# CoffeePID_EDA.net
KiCad netlist of a schematic drawn in EasyEDA
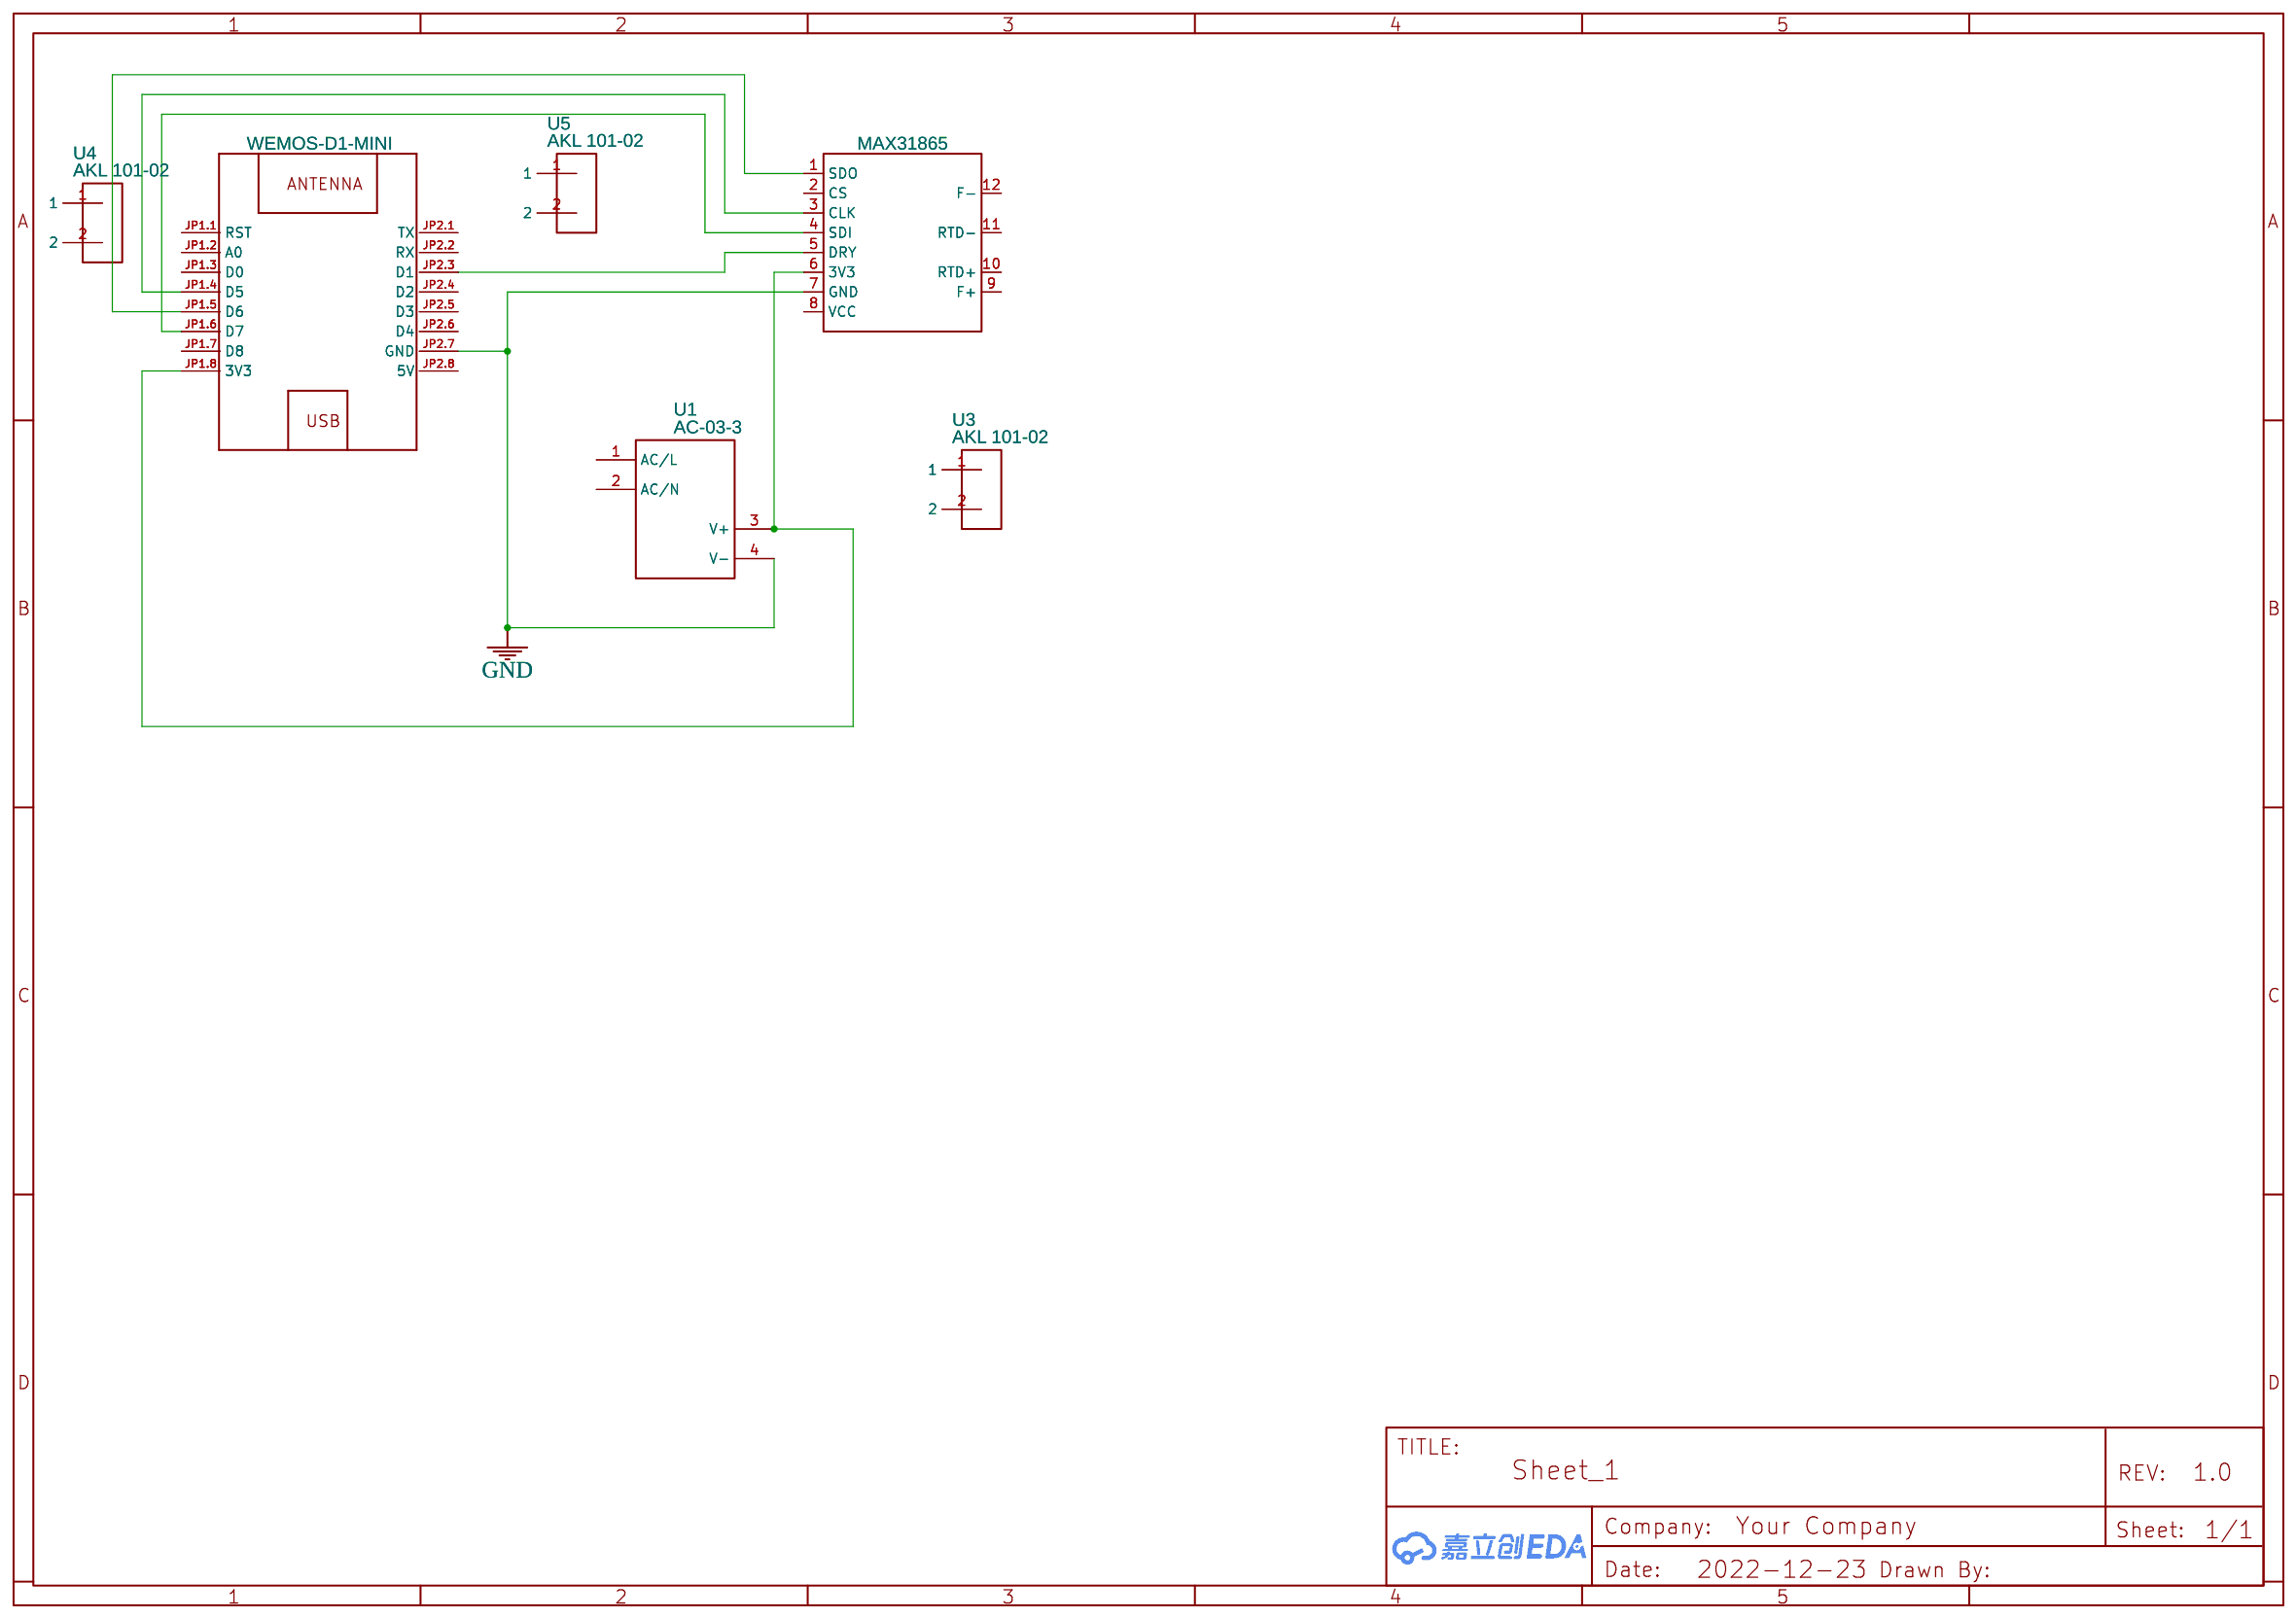
[diagram p0: Wemos D1]
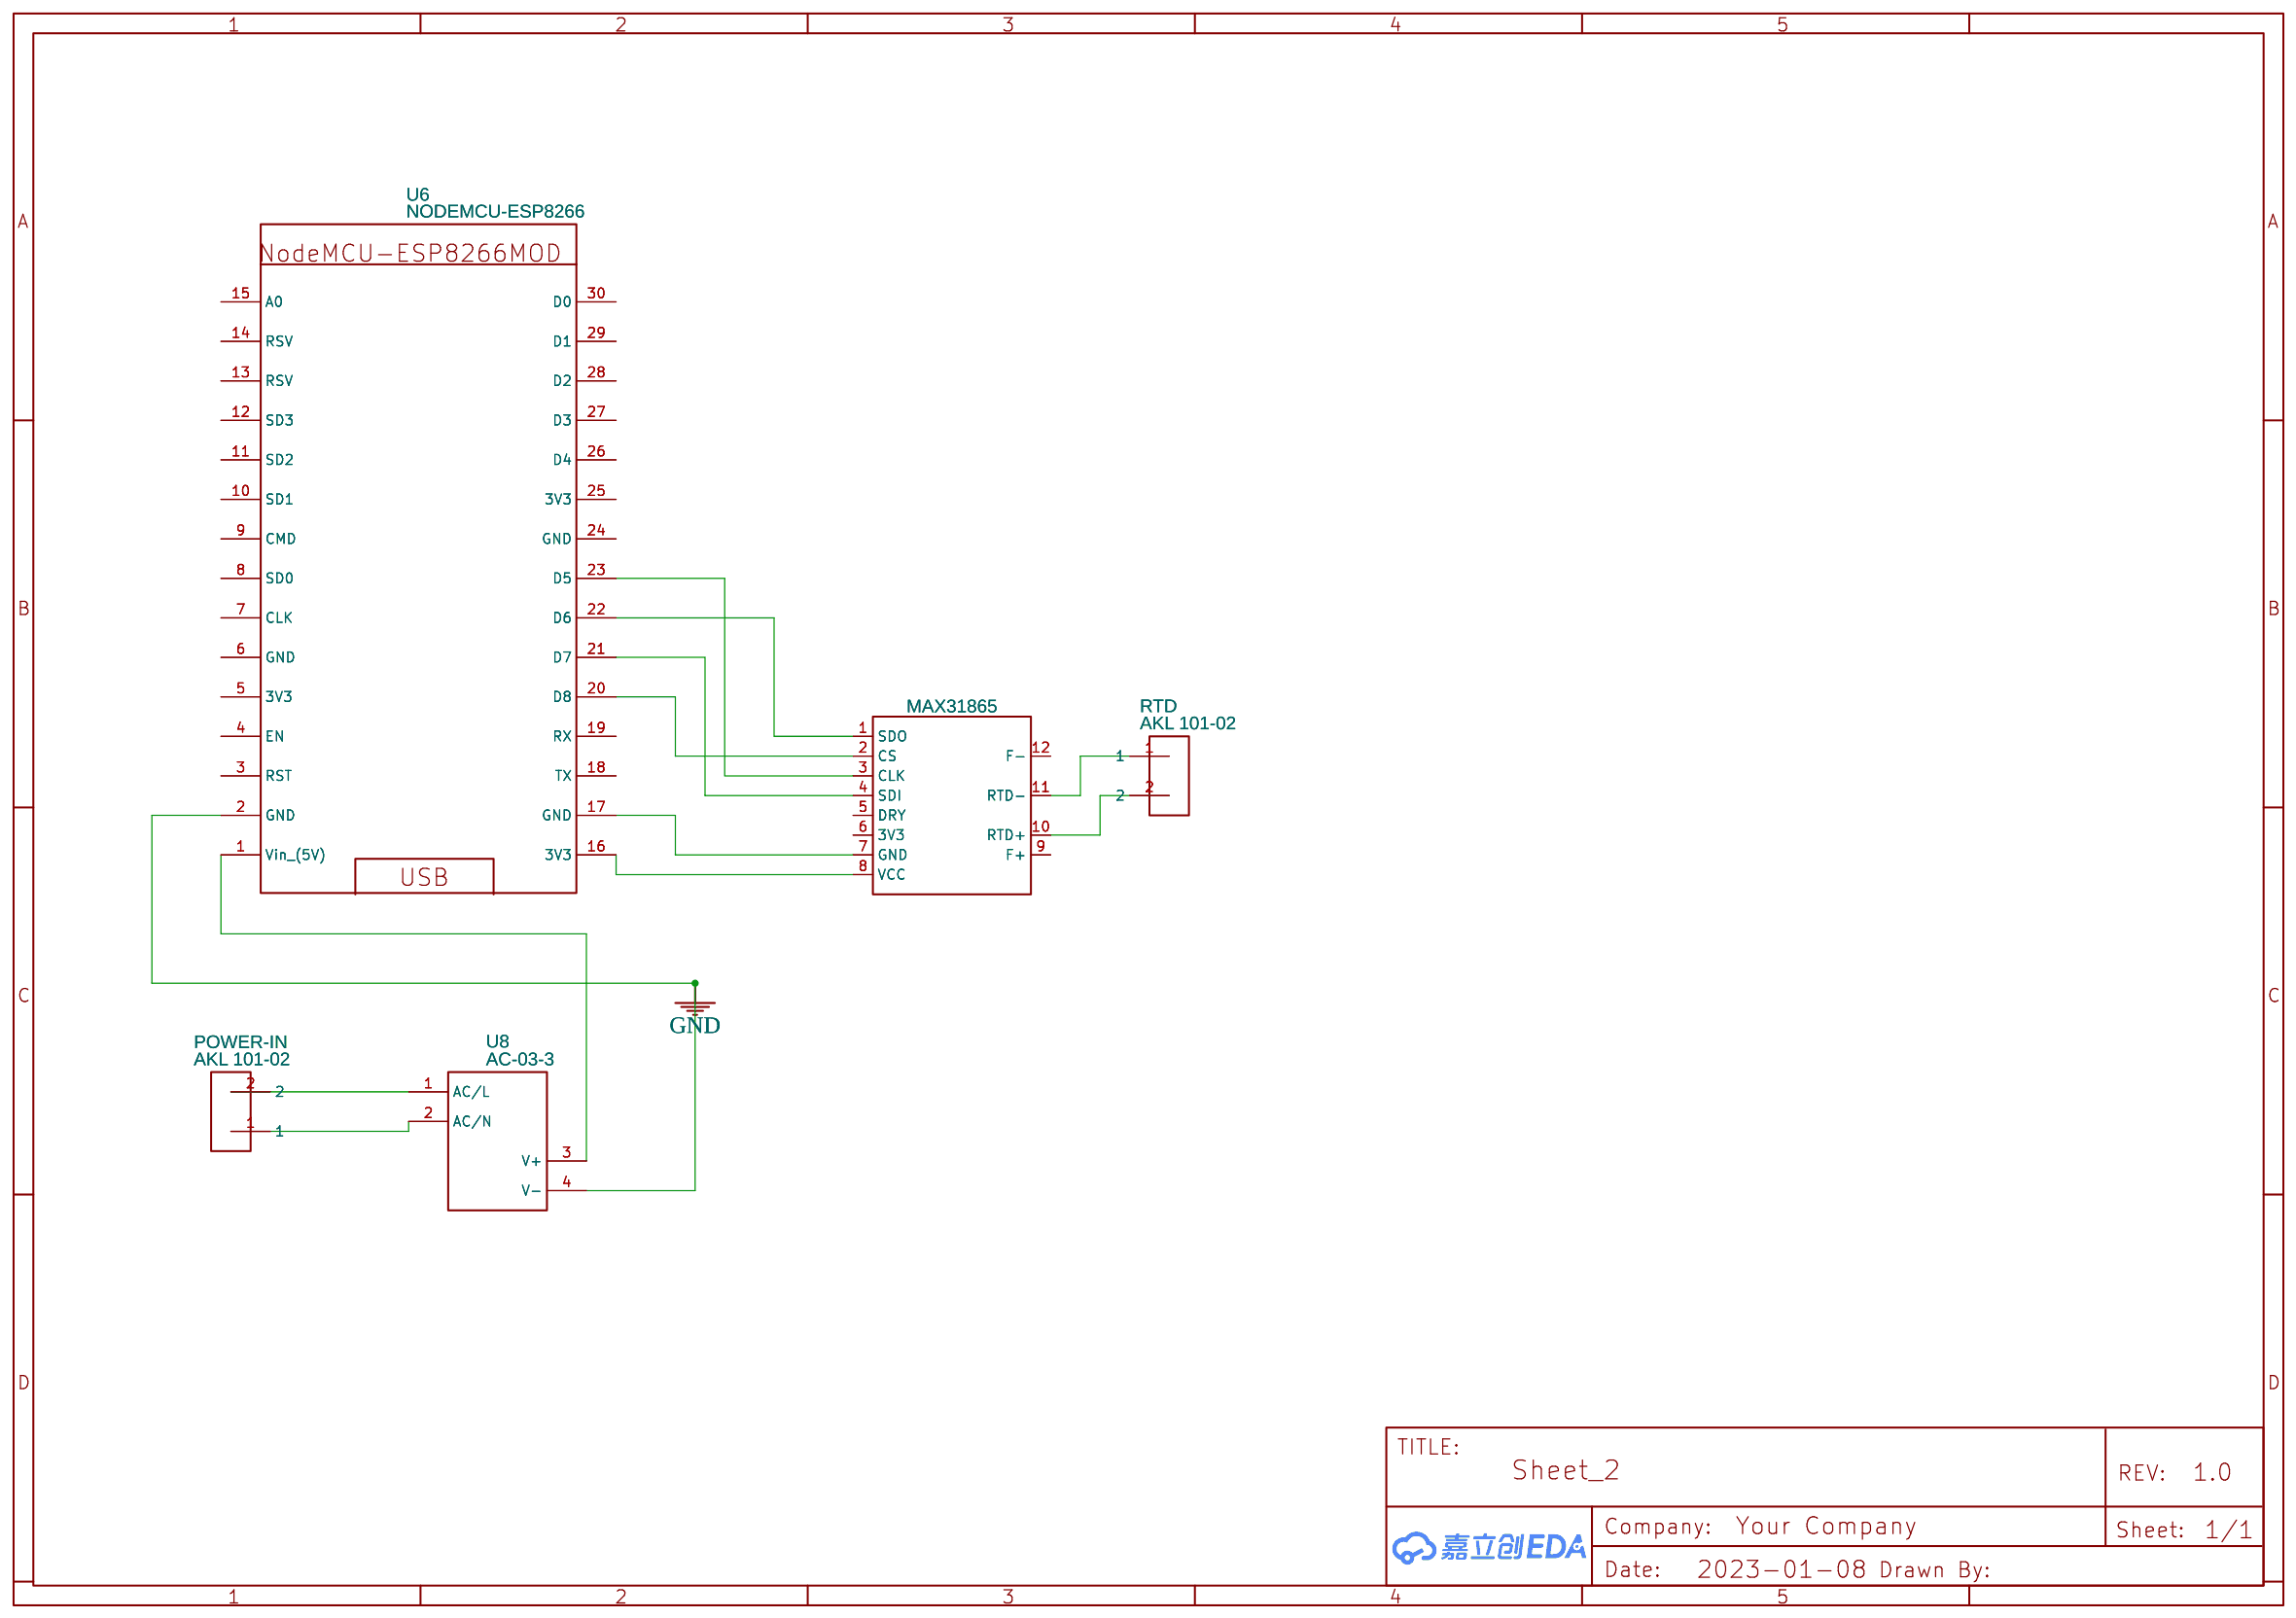
[diagram p1: NodeMCU]

(export (version "E")
  (design (tool "Eeschema 10.0.6"))
  (components
    (comp (ref "1") (value "WEMOS-D1-MINI") (libsource (lib "") (part "WEMOS-D1-MINI")))
    (comp (ref "U1")
      (value "AC-03-3")
      (fields
        (field (name "BOM_Manufacturer Part") "B07C4THP6G")
        (field (name "BOM_Supplier Part") "‎ 3x 220 V vers 3.3 V")
      )
      (libsource (lib "") (part "AC-03-3"))
    )
    (comp (ref "U2") (value "MAX31865") (libsource (lib "") (part "MAX31865")))
    (comp (ref "U3") (value "AKL 101-02") (libsource (lib "") (part "AKL 101-02")))
    (comp (ref "U4") (value "AKL 101-02") (libsource (lib "") (part "AKL 101-02")))
    (comp (ref "U5") (value "AKL 101-02") (libsource (lib "") (part "AKL 101-02")))
    (comp (ref "POWER-IN") (value "AKL 101-02") (libsource (lib "") (part "AKL 101-02")))
    (comp (ref "RTD") (value "AKL 101-02") (libsource (lib "") (part "AKL 101-02_1")))
    (comp (ref "U6")
      (value "NODEMCU-ESP8266")
      (fields
        (field (name "BOM_Manufacturer Part") "NodeMCU-8266")
        (field (name "BOM_Supplier Part") "C111436")
      )
      (libsource (lib "") (part "NODEMCU-ESP8266"))
    )
    (comp (ref "U8")
      (value "AC-03-3")
      (fields
        (field (name "BOM_Manufacturer Part") "B07C4THP6G")
        (field (name "BOM_Supplier Part") "‎ 3x 220 V vers 3.3 V")
      )
      (libsource (lib "") (part "AC-03-3"))
    )
    (comp (ref "U9") (value "MAX31865") (libsource (lib "") (part "MAX31865")))
  )
  (nets
    (net (code "1") (name "GND") (class "Default")
      (node (ref "1") (pin "JP2.7") (pinfunction "GND_JP2.7") (pintype "bidirectional"))
      (node (ref "U1") (pin "4") (pinfunction "V-_4") (pintype "unspecified"))
      (node (ref "U2") (pin "7") (pinfunction "GND_7") (pintype "unspecified"))
      (node (ref "U6") (pin "2") (pinfunction "GND_2") (pintype "unspecified"))
      (node (ref "U8") (pin "4") (pinfunction "V-_4") (pintype "unspecified"))
    )
    (net (code "2") (name "Net-(1-3V3)") (class "Default")
      (node (ref "1") (pin "JP1.8") (pinfunction "3V3_JP1.8") (pintype "bidirectional"))
      (node (ref "U1") (pin "3") (pinfunction "V+_3") (pintype "unspecified"))
      (node (ref "U2") (pin "6") (pinfunction "3V3_6") (pintype "unspecified"))
    )
    (net (code "3") (name "Net-(1-D1)") (class "Default")
      (node (ref "1") (pin "JP2.3") (pinfunction "D1_JP2.3") (pintype "bidirectional"))
      (node (ref "U2") (pin "5") (pinfunction "DRY_5") (pintype "unspecified"))
    )
    (net (code "4") (name "Net-(1-D5)") (class "Default")
      (node (ref "1") (pin "JP1.4") (pinfunction "D5_JP1.4") (pintype "bidirectional"))
      (node (ref "U2") (pin "3") (pinfunction "CLK_3") (pintype "unspecified"))
    )
    (net (code "5") (name "Net-(1-D6)") (class "Default")
      (node (ref "1") (pin "JP1.5") (pinfunction "D6_JP1.5") (pintype "bidirectional"))
      (node (ref "U2") (pin "1") (pinfunction "SDO_1") (pintype "unspecified"))
    )
    (net (code "6") (name "Net-(1-D7)") (class "Default")
      (node (ref "1") (pin "JP1.6") (pinfunction "D7_JP1.6") (pintype "bidirectional"))
      (node (ref "U2") (pin "4") (pinfunction "SDI_4") (pintype "unspecified"))
    )
    (net (code "7") (name "Net-(U6-D5)") (class "Default")
      (node (ref "U6") (pin "23") (pinfunction "D5_23") (pintype "unspecified"))
      (node (ref "U9") (pin "3") (pinfunction "CLK_3") (pintype "unspecified"))
    )
    (net (code "8") (name "Net-(U6-D6)") (class "Default")
      (node (ref "U6") (pin "22") (pinfunction "D6_22") (pintype "unspecified"))
      (node (ref "U9") (pin "1") (pinfunction "SDO_1") (pintype "unspecified"))
    )
    (net (code "9") (name "Net-(U6-D7)") (class "Default")
      (node (ref "U6") (pin "21") (pinfunction "D7_21") (pintype "unspecified"))
      (node (ref "U9") (pin "4") (pinfunction "SDI_4") (pintype "unspecified"))
    )
    (net (code "10") (name "Net-(U6-D8)") (class "Default")
      (node (ref "U6") (pin "20") (pinfunction "D8_20") (pintype "unspecified"))
      (node (ref "U9") (pin "2") (pinfunction "CS_2") (pintype "unspecified"))
    )
    (net (code "11") (name "Net-(U6-Vin_(5V))") (class "Default")
      (node (ref "U6") (pin "1") (pinfunction "Vin_(5V)_1") (pintype "unspecified"))
      (node (ref "U8") (pin "3") (pinfunction "V+_3") (pintype "unspecified"))
    )
    (net (code "12") (name "Net-(U8-AC{slash}L)") (class "Default")
      (node (ref "POWER-IN") (pin "2") (pinfunction "2_2") (pintype "unspecified"))
      (node (ref "U8") (pin "1") (pinfunction "AC/L_1") (pintype "unspecified"))
    )
    (net (code "13") (name "Net-(U8-AC{slash}N)") (class "Default")
      (node (ref "POWER-IN") (pin "1") (pinfunction "1_1") (pintype "unspecified"))
      (node (ref "U8") (pin "2") (pinfunction "AC/N_2") (pintype "unspecified"))
    )
    (net (code "14") (name "Net-(U9-GND)") (class "Default")
      (node (ref "U6") (pin "17") (pinfunction "GND_17") (pintype "unspecified"))
      (node (ref "U9") (pin "7") (pinfunction "GND_7") (pintype "unspecified"))
    )
    (net (code "15") (name "Net-(U9-RTD+)") (class "Default")
      (node (ref "RTD") (pin "2") (pinfunction "2_2") (pintype "unspecified"))
      (node (ref "U9") (pin "10") (pinfunction "RTD+_10") (pintype "unspecified"))
    )
    (net (code "16") (name "Net-(U9-RTD-)") (class "Default")
      (node (ref "RTD") (pin "1") (pinfunction "1_1") (pintype "unspecified"))
      (node (ref "U9") (pin "11") (pinfunction "RTD-_11") (pintype "unspecified"))
    )
    (net (code "17") (name "Net-(U9-VCC)") (class "Default")
      (node (ref "U6") (pin "16") (pinfunction "3V3_16") (pintype "unspecified"))
      (node (ref "U9") (pin "8") (pinfunction "VCC_8") (pintype "unspecified"))
    )
    (net (code "18") (name "unconnected-(1-5V-PadJP2.8)") (class "Default")
      (node (ref "1") (pin "JP2.8") (pinfunction "5V_JP2.8") (pintype "bidirectional"))
    )
    (net (code "19") (name "unconnected-(1-A0-PadJP1.2)") (class "Default")
      (node (ref "1") (pin "JP1.2") (pinfunction "A0_JP1.2") (pintype "bidirectional"))
    )
    (net (code "20") (name "unconnected-(1-D0-PadJP1.3)") (class "Default")
      (node (ref "1") (pin "JP1.3") (pinfunction "D0_JP1.3") (pintype "bidirectional"))
    )
    (net (code "21") (name "unconnected-(1-D2-PadJP2.4)") (class "Default")
      (node (ref "1") (pin "JP2.4") (pinfunction "D2_JP2.4") (pintype "bidirectional"))
    )
    (net (code "22") (name "unconnected-(1-D3-PadJP2.5)") (class "Default")
      (node (ref "1") (pin "JP2.5") (pinfunction "D3_JP2.5") (pintype "bidirectional"))
    )
    (net (code "23") (name "unconnected-(1-D4-PadJP2.6)") (class "Default")
      (node (ref "1") (pin "JP2.6") (pinfunction "D4_JP2.6") (pintype "bidirectional"))
    )
    (net (code "24") (name "unconnected-(1-D8-PadJP1.7)") (class "Default")
      (node (ref "1") (pin "JP1.7") (pinfunction "D8_JP1.7") (pintype "bidirectional"))
    )
    (net (code "25") (name "unconnected-(1-RST-PadJP1.1)") (class "Default")
      (node (ref "1") (pin "JP1.1") (pinfunction "RST_JP1.1") (pintype "bidirectional"))
    )
    (net (code "26") (name "unconnected-(1-RX-PadJP2.2)") (class "Default")
      (node (ref "1") (pin "JP2.2") (pinfunction "RX_JP2.2") (pintype "bidirectional"))
    )
    (net (code "27") (name "unconnected-(1-TX-PadJP2.1)") (class "Default")
      (node (ref "1") (pin "JP2.1") (pinfunction "TX_JP2.1") (pintype "bidirectional"))
    )
    (net (code "28") (name "unconnected-(U1-AC{slash}L-Pad1)") (class "Default")
      (node (ref "U1") (pin "1") (pinfunction "AC/L_1") (pintype "unspecified"))
    )
    (net (code "29") (name "unconnected-(U1-AC{slash}N-Pad2)") (class "Default")
      (node (ref "U1") (pin "2") (pinfunction "AC/N_2") (pintype "unspecified"))
    )
    (net (code "30") (name "unconnected-(U2-CS-Pad2)") (class "Default")
      (node (ref "U2") (pin "2") (pinfunction "CS_2") (pintype "unspecified"))
    )
    (net (code "31") (name "unconnected-(U2-F+-Pad9)") (class "Default")
      (node (ref "U2") (pin "9") (pinfunction "F+_9") (pintype "unspecified"))
    )
    (net (code "32") (name "unconnected-(U2-F--Pad12)") (class "Default")
      (node (ref "U2") (pin "12") (pinfunction "F-_12") (pintype "unspecified"))
    )
    (net (code "33") (name "unconnected-(U2-RTD+-Pad10)") (class "Default")
      (node (ref "U2") (pin "10") (pinfunction "RTD+_10") (pintype "unspecified"))
    )
    (net (code "34") (name "unconnected-(U2-RTD--Pad11)") (class "Default")
      (node (ref "U2") (pin "11") (pinfunction "RTD-_11") (pintype "unspecified"))
    )
    (net (code "35") (name "unconnected-(U2-VCC-Pad8)") (class "Default")
      (node (ref "U2") (pin "8") (pinfunction "VCC_8") (pintype "unspecified"))
    )
    (net (code "36") (name "unconnected-(U3-Pad1)") (class "Default")
      (node (ref "U3") (pin "1") (pinfunction "1_1") (pintype "unspecified"))
    )
    (net (code "37") (name "unconnected-(U3-Pad2)") (class "Default")
      (node (ref "U3") (pin "2") (pinfunction "2_2") (pintype "unspecified"))
    )
    (net (code "38") (name "unconnected-(U4-Pad1)") (class "Default")
      (node (ref "U4") (pin "1") (pinfunction "1_1") (pintype "unspecified"))
    )
    (net (code "39") (name "unconnected-(U4-Pad2)") (class "Default")
      (node (ref "U4") (pin "2") (pinfunction "2_2") (pintype "unspecified"))
    )
    (net (code "40") (name "unconnected-(U5-Pad1)") (class "Default")
      (node (ref "U5") (pin "1") (pinfunction "1_1") (pintype "unspecified"))
    )
    (net (code "41") (name "unconnected-(U5-Pad2)") (class "Default")
      (node (ref "U5") (pin "2") (pinfunction "2_2") (pintype "unspecified"))
    )
    (net (code "42") (name "unconnected-(U6-3V3-Pad5)") (class "Default")
      (node (ref "U6") (pin "5") (pinfunction "3V3_5") (pintype "unspecified"))
    )
    (net (code "43") (name "unconnected-(U6-3V3-Pad25)") (class "Default")
      (node (ref "U6") (pin "25") (pinfunction "3V3_25") (pintype "unspecified"))
    )
    (net (code "44") (name "unconnected-(U6-A0-Pad15)") (class "Default")
      (node (ref "U6") (pin "15") (pinfunction "A0_15") (pintype "unspecified"))
    )
    (net (code "45") (name "unconnected-(U6-CLK-Pad7)") (class "Default")
      (node (ref "U6") (pin "7") (pinfunction "CLK_7") (pintype "unspecified"))
    )
    (net (code "46") (name "unconnected-(U6-CMD-Pad9)") (class "Default")
      (node (ref "U6") (pin "9") (pinfunction "CMD_9") (pintype "unspecified"))
    )
    (net (code "47") (name "unconnected-(U6-D0-Pad30)") (class "Default")
      (node (ref "U6") (pin "30") (pinfunction "D0_30") (pintype "unspecified"))
    )
    (net (code "48") (name "unconnected-(U6-D1-Pad29)") (class "Default")
      (node (ref "U6") (pin "29") (pinfunction "D1_29") (pintype "unspecified"))
    )
    (net (code "49") (name "unconnected-(U6-D2-Pad28)") (class "Default")
      (node (ref "U6") (pin "28") (pinfunction "D2_28") (pintype "unspecified"))
    )
    (net (code "50") (name "unconnected-(U6-D3-Pad27)") (class "Default")
      (node (ref "U6") (pin "27") (pinfunction "D3_27") (pintype "unspecified"))
    )
    (net (code "51") (name "unconnected-(U6-D4-Pad26)") (class "Default")
      (node (ref "U6") (pin "26") (pinfunction "D4_26") (pintype "unspecified"))
    )
    (net (code "52") (name "unconnected-(U6-EN-Pad4)") (class "Default")
      (node (ref "U6") (pin "4") (pinfunction "EN_4") (pintype "unspecified"))
    )
    (net (code "53") (name "unconnected-(U6-GND-Pad6)") (class "Default")
      (node (ref "U6") (pin "6") (pinfunction "GND_6") (pintype "unspecified"))
    )
    (net (code "54") (name "unconnected-(U6-GND-Pad24)") (class "Default")
      (node (ref "U6") (pin "24") (pinfunction "GND_24") (pintype "unspecified"))
    )
    (net (code "55") (name "unconnected-(U6-RST-Pad3)") (class "Default")
      (node (ref "U6") (pin "3") (pinfunction "RST_3") (pintype "unspecified"))
    )
    (net (code "56") (name "unconnected-(U6-RSV-Pad13)") (class "Default")
      (node (ref "U6") (pin "13") (pinfunction "RSV_13") (pintype "unspecified"))
    )
    (net (code "57") (name "unconnected-(U6-RSV-Pad14)") (class "Default")
      (node (ref "U6") (pin "14") (pinfunction "RSV_14") (pintype "unspecified"))
    )
    (net (code "58") (name "unconnected-(U6-RX-Pad19)") (class "Default")
      (node (ref "U6") (pin "19") (pinfunction "RX_19") (pintype "unspecified"))
    )
    (net (code "59") (name "unconnected-(U6-SD0-Pad8)") (class "Default")
      (node (ref "U6") (pin "8") (pinfunction "SD0_8") (pintype "unspecified"))
    )
    (net (code "60") (name "unconnected-(U6-SD1-Pad10)") (class "Default")
      (node (ref "U6") (pin "10") (pinfunction "SD1_10") (pintype "unspecified"))
    )
    (net (code "61") (name "unconnected-(U6-SD2-Pad11)") (class "Default")
      (node (ref "U6") (pin "11") (pinfunction "SD2_11") (pintype "unspecified"))
    )
    (net (code "62") (name "unconnected-(U6-SD3-Pad12)") (class "Default")
      (node (ref "U6") (pin "12") (pinfunction "SD3_12") (pintype "unspecified"))
    )
    (net (code "63") (name "unconnected-(U6-TX-Pad18)") (class "Default")
      (node (ref "U6") (pin "18") (pinfunction "TX_18") (pintype "unspecified"))
    )
    (net (code "64") (name "unconnected-(U9-3V3-Pad6)") (class "Default")
      (node (ref "U9") (pin "6") (pinfunction "3V3_6") (pintype "unspecified"))
    )
    (net (code "65") (name "unconnected-(U9-DRY-Pad5)") (class "Default")
      (node (ref "U9") (pin "5") (pinfunction "DRY_5") (pintype "unspecified"))
    )
    (net (code "66") (name "unconnected-(U9-F+-Pad9)") (class "Default")
      (node (ref "U9") (pin "9") (pinfunction "F+_9") (pintype "unspecified"))
    )
    (net (code "67") (name "unconnected-(U9-F--Pad12)") (class "Default")
      (node (ref "U9") (pin "12") (pinfunction "F-_12") (pintype "unspecified"))
    )
  )
)
